# mbot_command_link.net
KiCad netlist of a schematic drawn in EasyEDA Pro
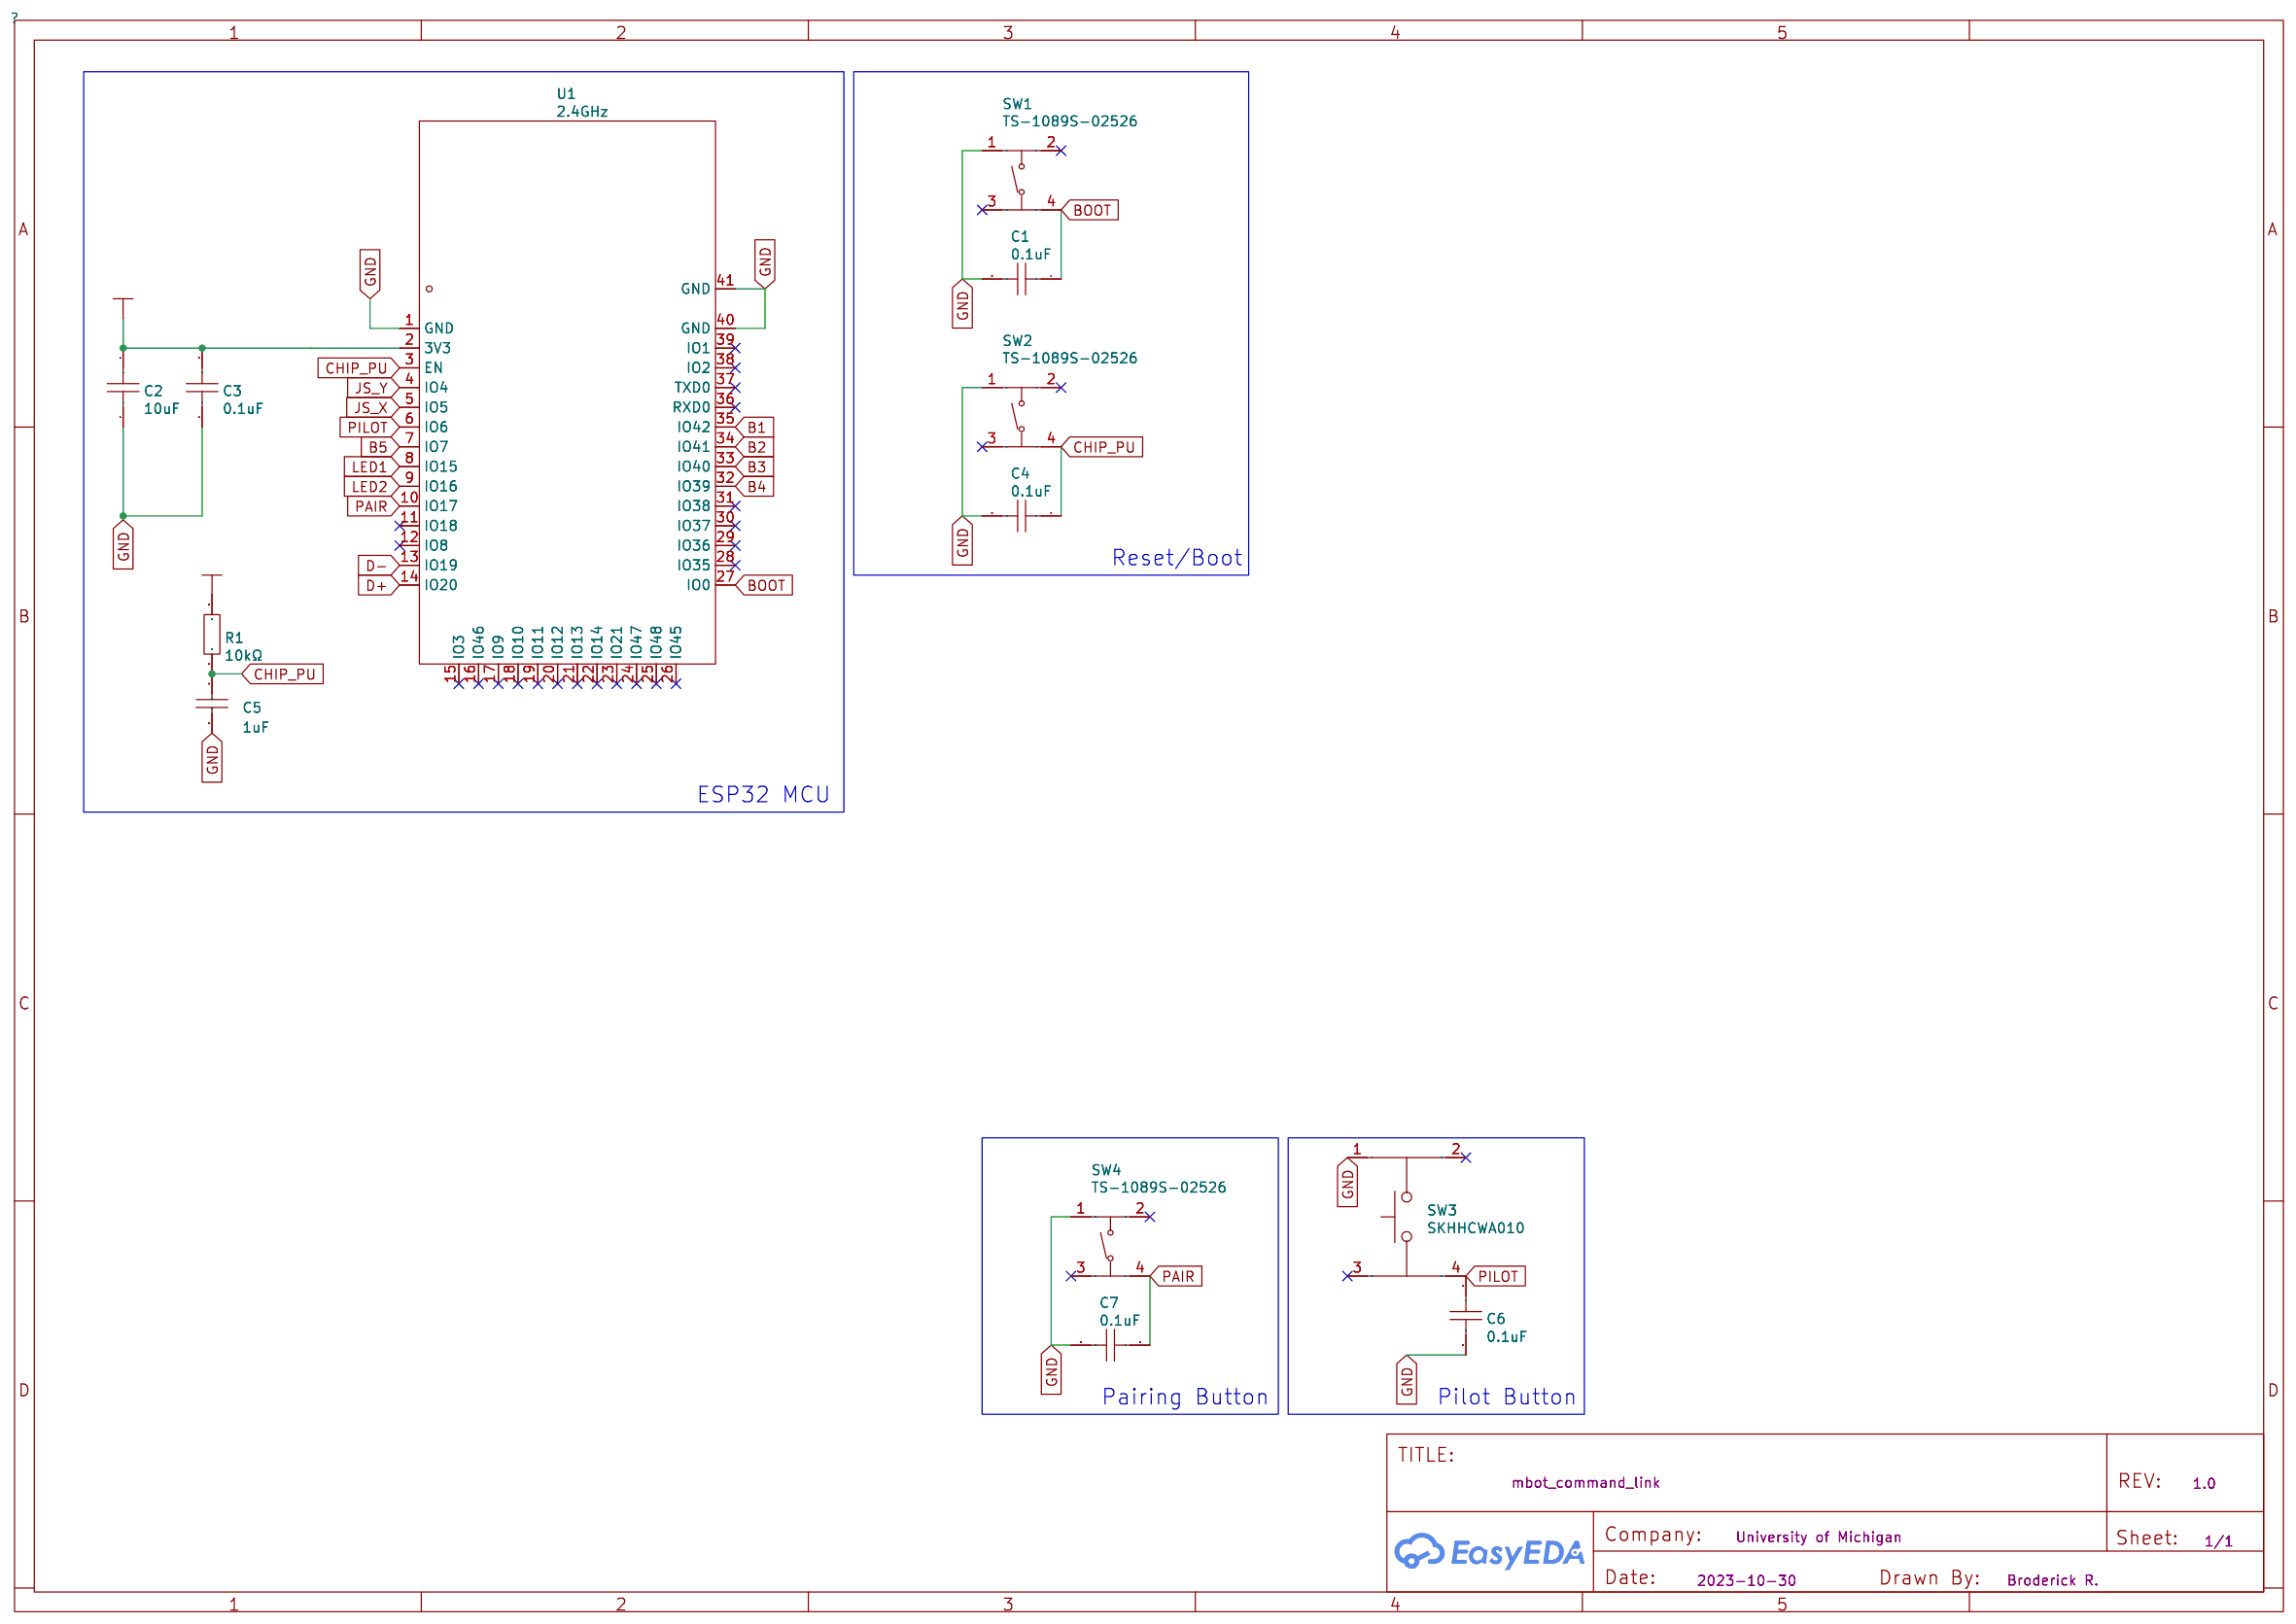
[diagram p0: MCU]
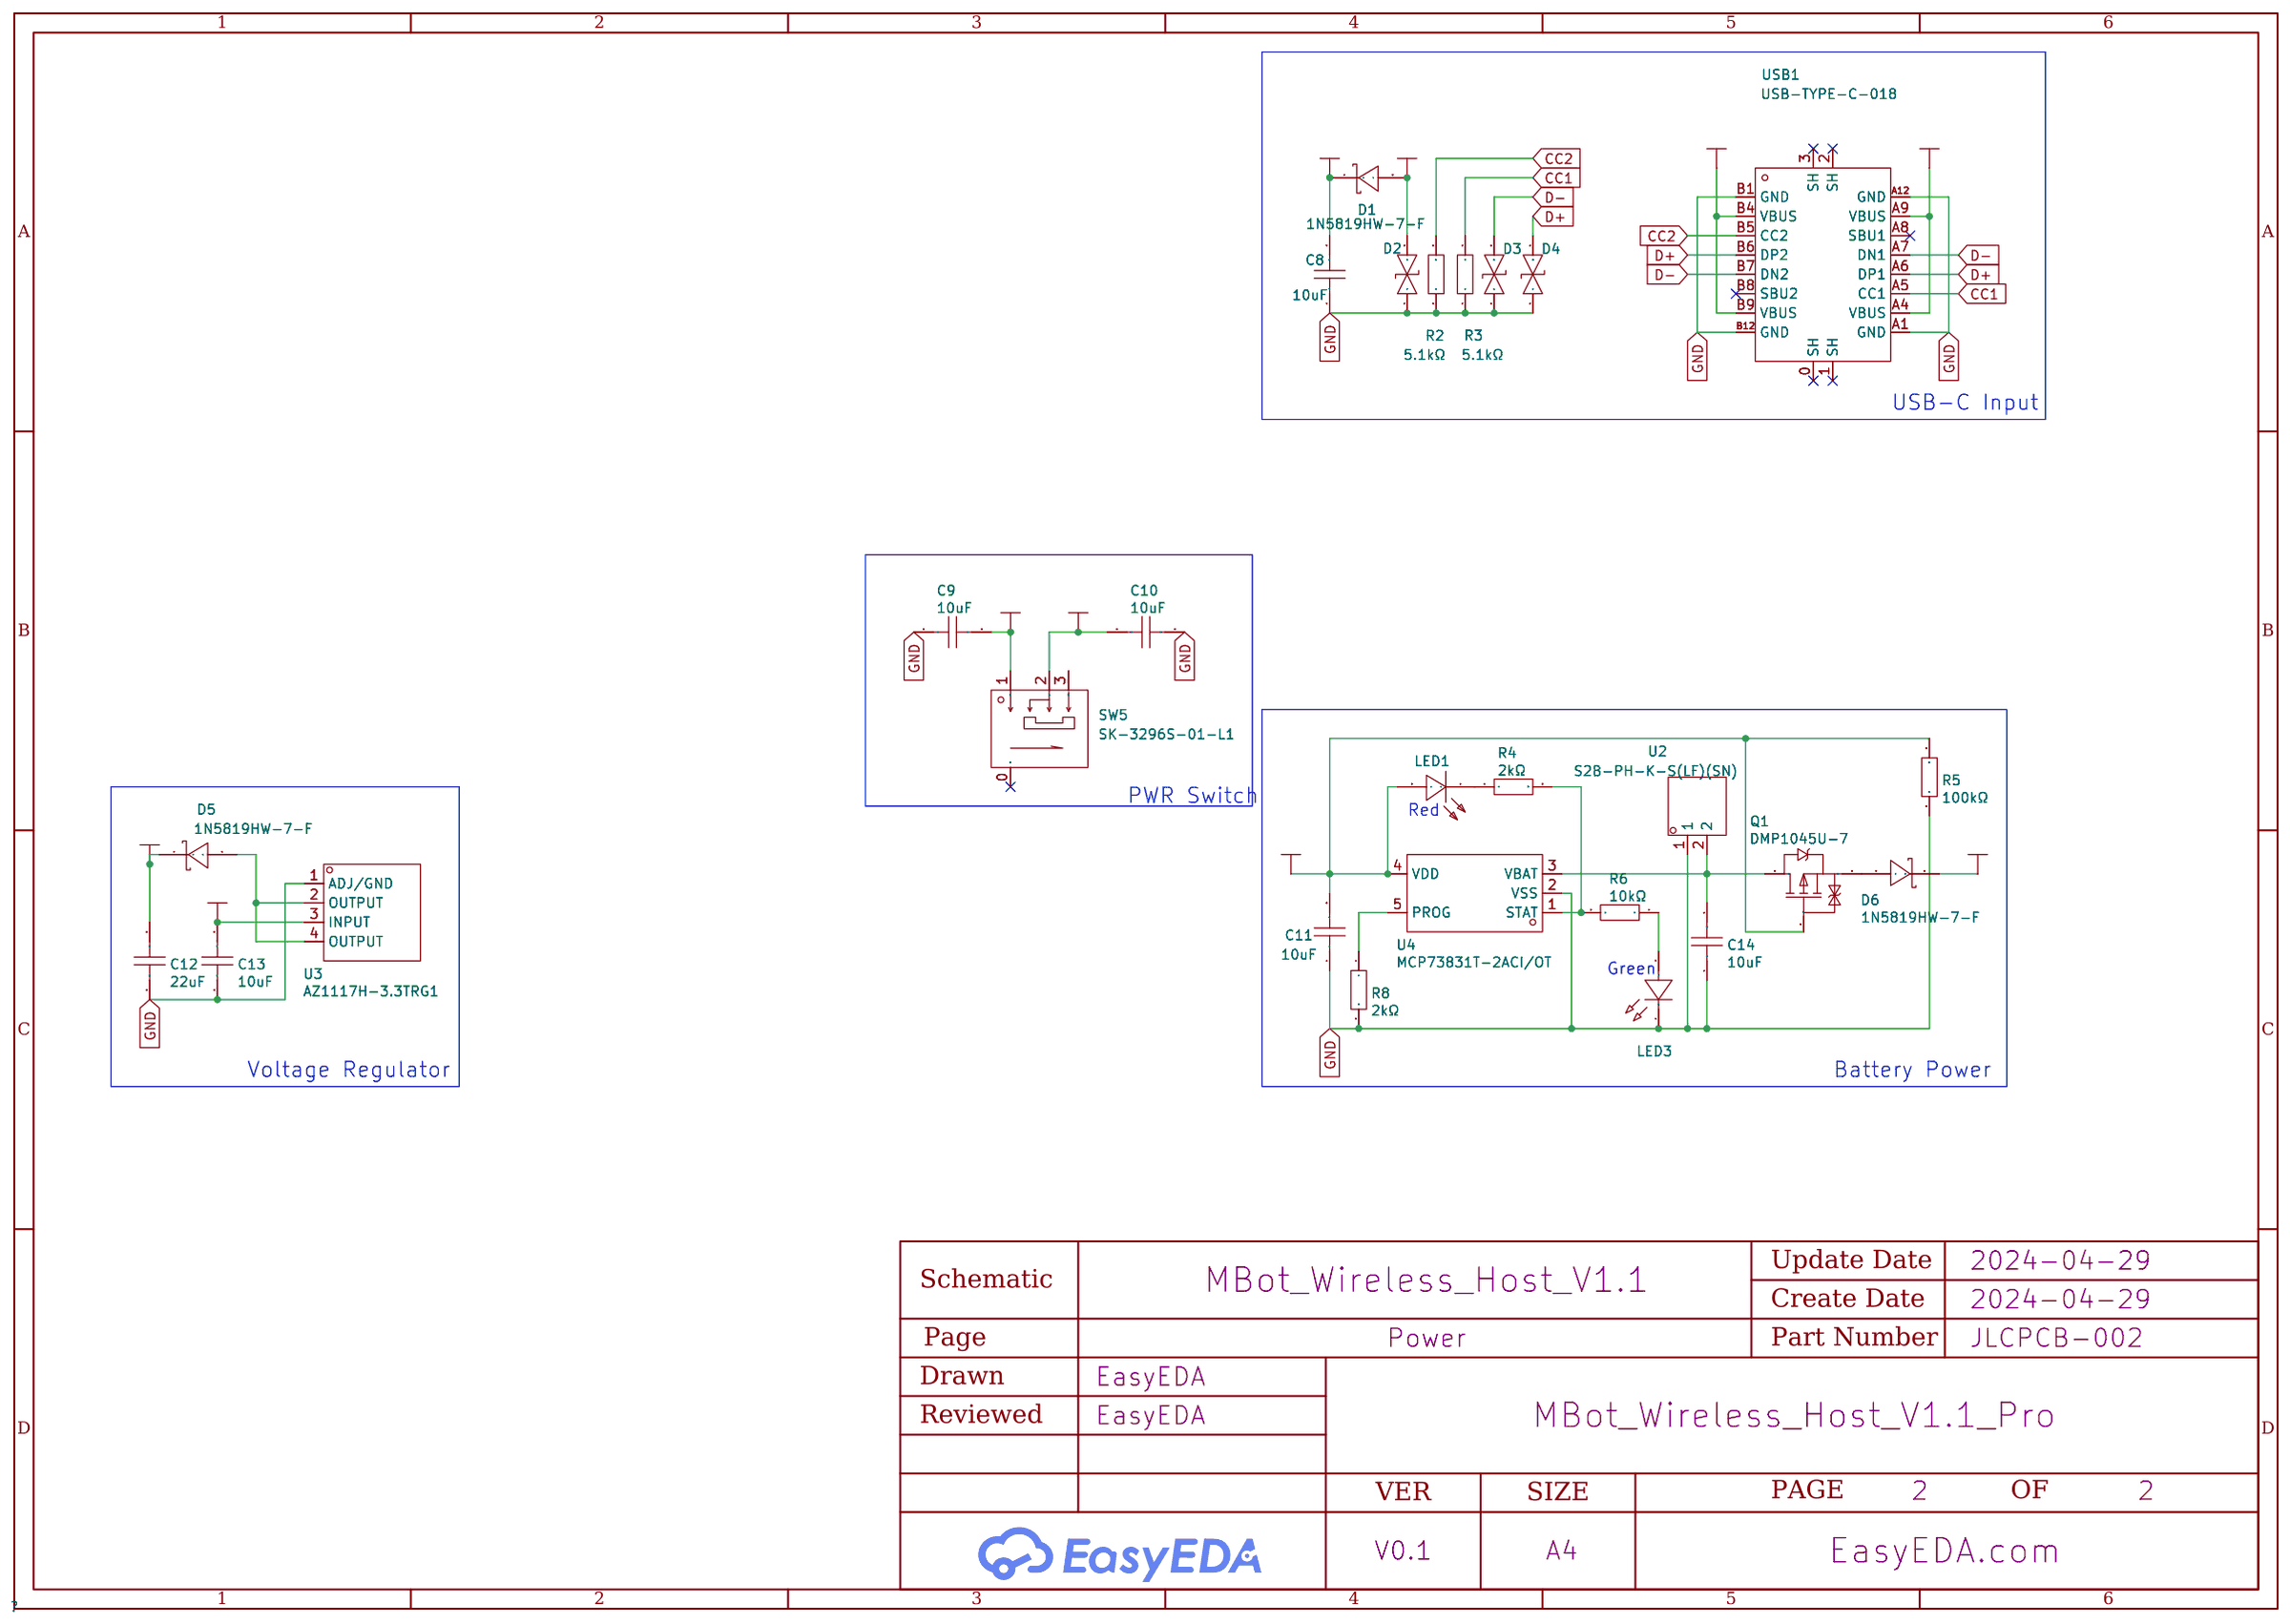
[diagram p1: Power]
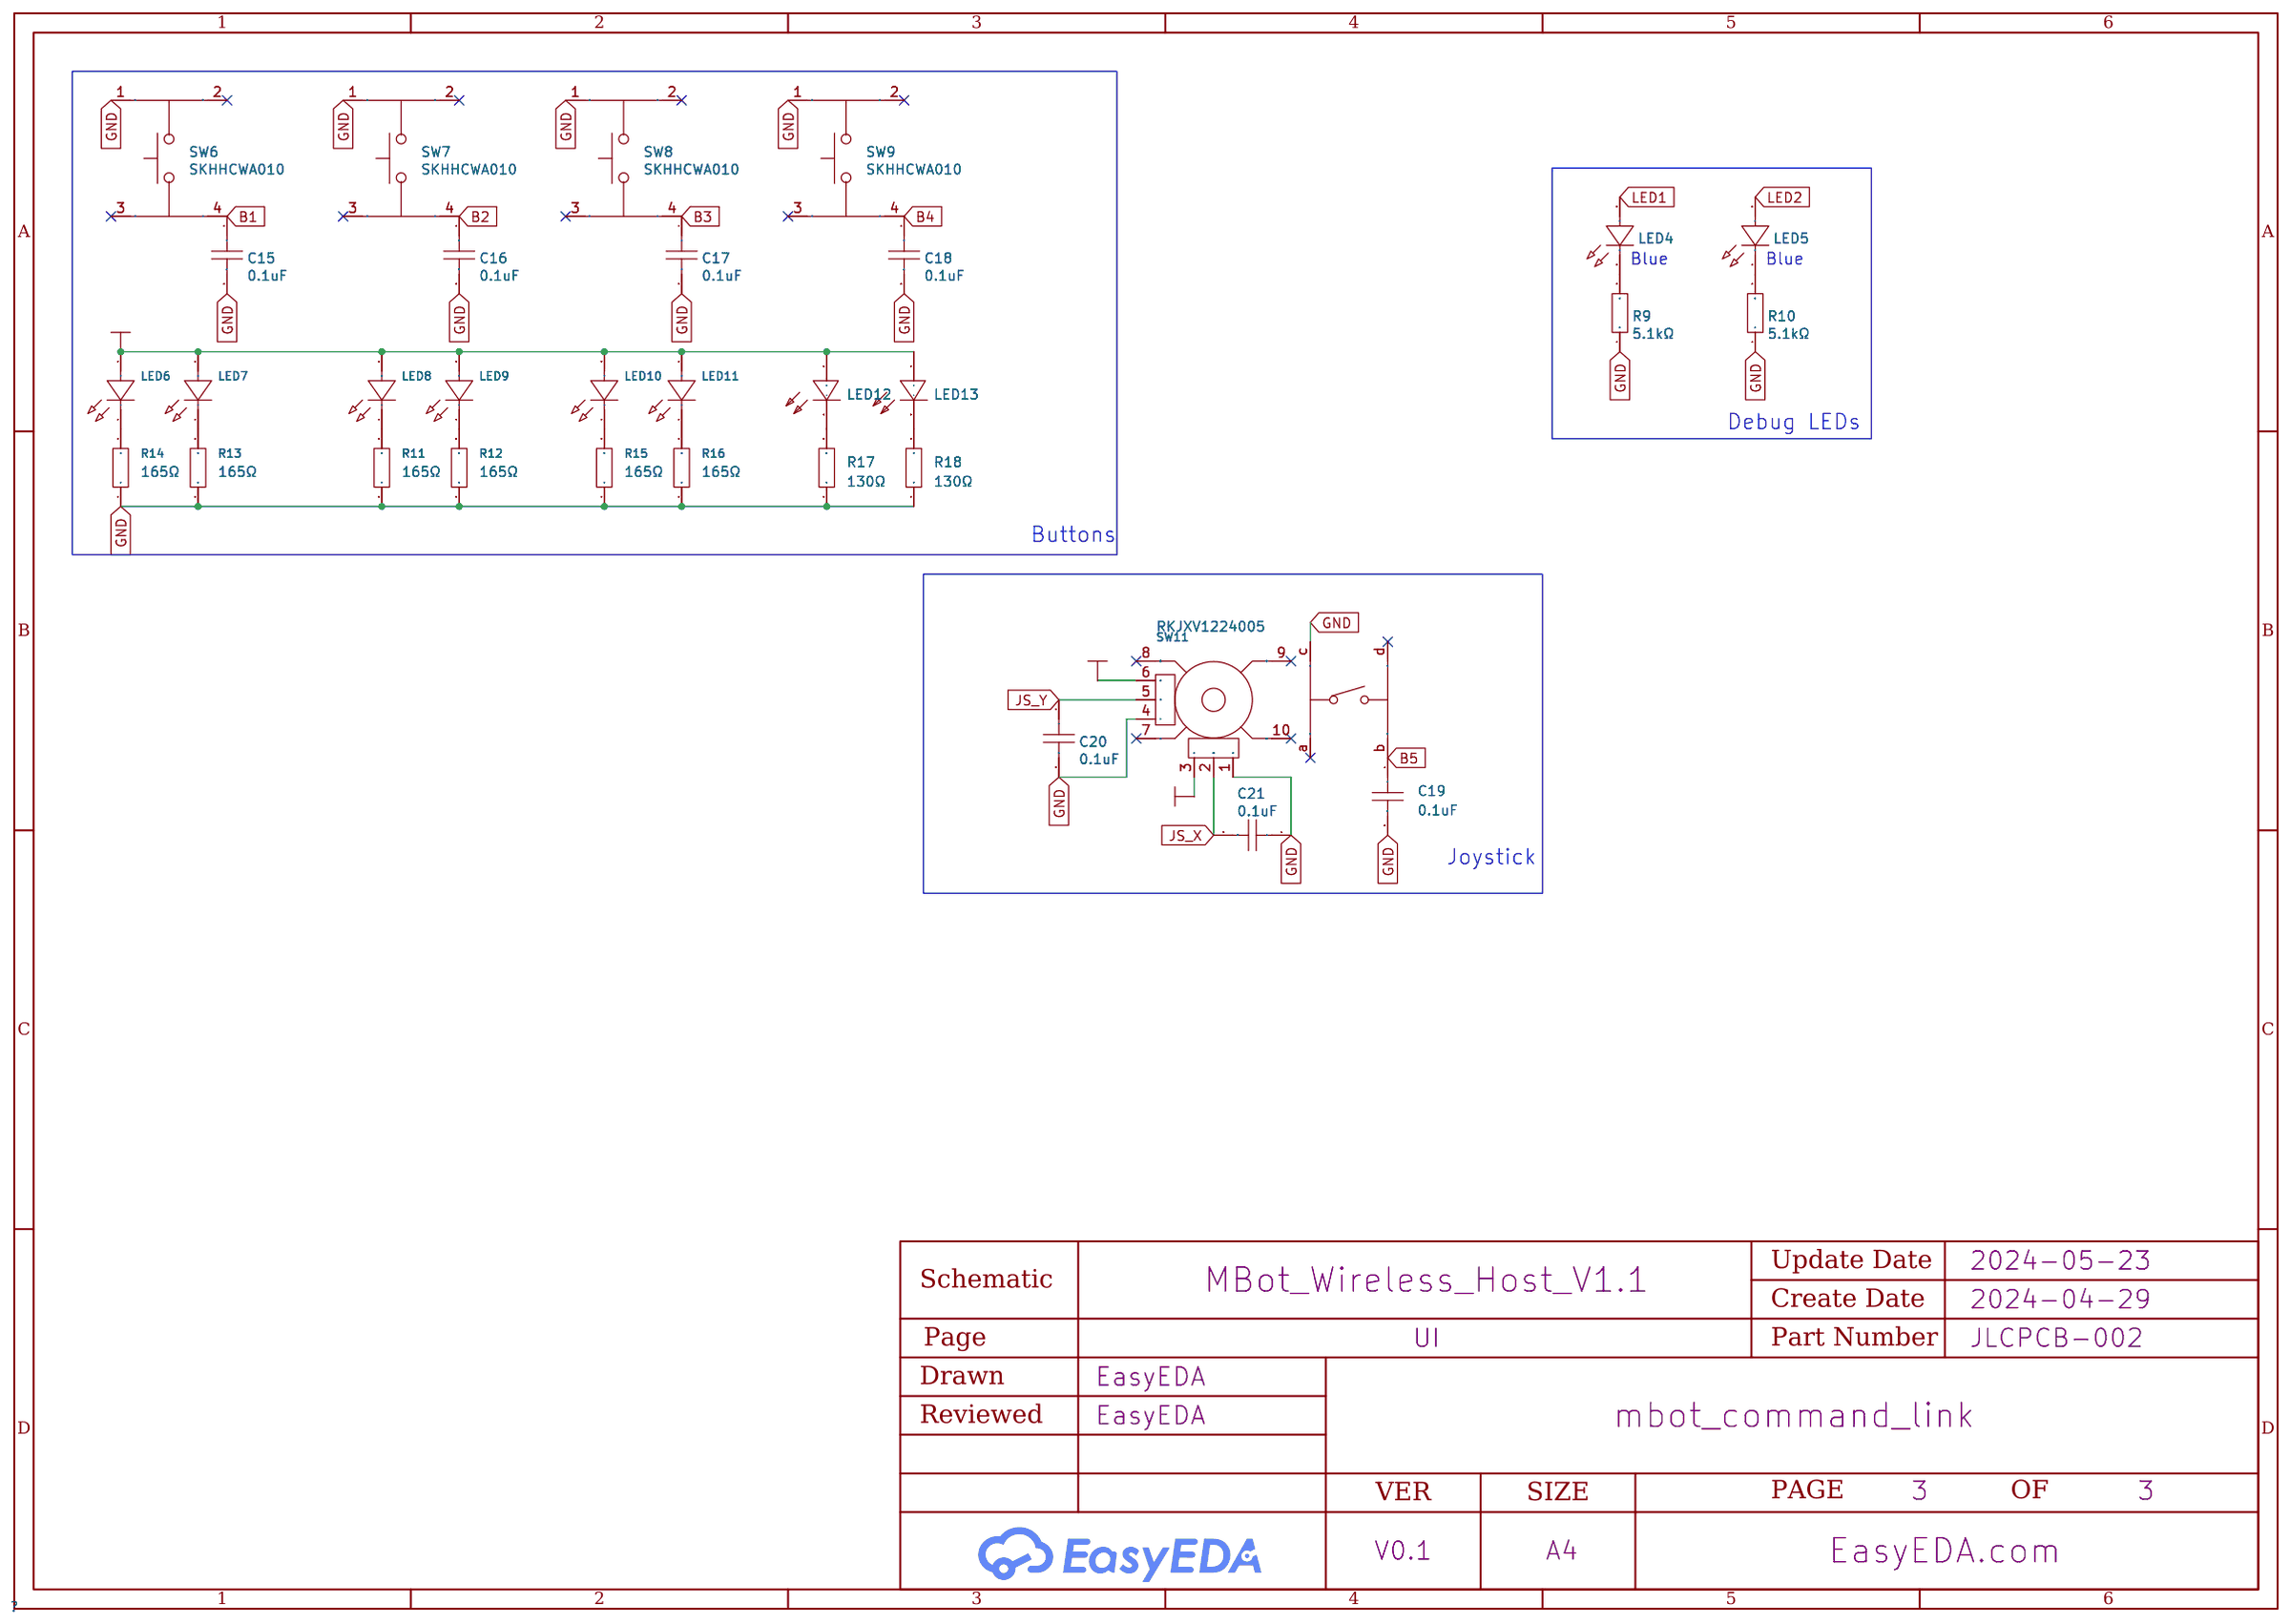
[diagram p2: UI]

(export (version "E")
  (design (tool "Eeschema 10.0.6"))
  (components
    (comp (ref "C1")
      (value "0.1uF")
      (footprint "easyedapro:footprint_52c0")
      (fields
        (field (name "Manufacturer Part") "CC0603KRX7R9BB104")
        (field (name "Manufacturer") "YAGEO(国巨)")
      )
      (libsource (lib "easyedapro") (part "0.1uF"))
    )
    (comp (ref "C2")
      (value "10uF")
      (footprint "easyedapro:footprint_52c0")
      (fields
        (field (name "Manufacturer Part") "CL10A106KP8NNNC")
        (field (name "Manufacturer") "SAMSUNG(三星)")
      )
      (libsource (lib "easyedapro") (part "10uF"))
    )
    (comp (ref "C3")
      (value "0.1uF")
      (footprint "easyedapro:footprint_52c0")
      (fields
        (field (name "Manufacturer Part") "CC0603KRX7R9BB104")
        (field (name "Manufacturer") "YAGEO(国巨)")
      )
      (libsource (lib "easyedapro") (part "0.1uF"))
    )
    (comp (ref "C4")
      (value "0.1uF")
      (footprint "easyedapro:footprint_52c0")
      (fields
        (field (name "Manufacturer Part") "CC0603KRX7R9BB104")
        (field (name "Manufacturer") "YAGEO(国巨)")
      )
      (libsource (lib "easyedapro") (part "0.1uF"))
    )
    (comp (ref "C5")
      (value "1uF")
      (footprint "easyedapro:C0603")
      (fields
        (field (name "Manufacturer Part") "CL10A105KO8NNNC")
        (field (name "Manufacturer") "SAMSUNG(三星)")
      )
      (libsource (lib "easyedapro") (part "CL10A105KO8NNNC"))
    )
    (comp (ref "C6")
      (value "0.1uF")
      (footprint "easyedapro:footprint_52c0")
      (fields
        (field (name "Manufacturer Part") "CC0603KRX7R9BB104")
        (field (name "Manufacturer") "YAGEO(国巨)")
      )
      (libsource (lib "easyedapro") (part "0.1uF"))
    )
    (comp (ref "C7")
      (value "0.1uF")
      (footprint "easyedapro:footprint_52c0")
      (fields
        (field (name "Manufacturer Part") "CC0603KRX7R9BB104")
        (field (name "Manufacturer") "YAGEO(国巨)")
      )
      (libsource (lib "easyedapro") (part "0.1uF"))
    )
    (comp (ref "R1")
      (value "10kΩ")
      (footprint "easyedapro:footprint_0432")
      (fields
        (field (name "Manufacturer Part") "0603WAF1002T5E")
        (field (name "Manufacturer") "UNI-ROYAL(厚声)")
      )
      (libsource (lib "easyedapro") (part "10kΩ"))
    )
    (comp (ref "SW1")
      (value "TS-1089S-02526")
      (footprint "easyedapro:footprint_4ab8")
      (fields (field (name "Manufacturer") "XUNPU(讯普)"))
      (libsource (lib "easyedapro") (part "TS-1089S-02526"))
    )
    (comp (ref "SW2")
      (value "TS-1089S-02526")
      (footprint "easyedapro:footprint_4ab8")
      (fields (field (name "Manufacturer") "XUNPU(讯普)"))
      (libsource (lib "easyedapro") (part "TS-1089S-02526"))
    )
    (comp (ref "SW3")
      (value "SKHHCWA010")
      (footprint "easyedapro:footprint_5a2e")
      (fields (field (name "Manufacturer") "ALPSALPINE(阿尔卑斯阿尔派)"))
      (libsource (lib "easyedapro") (part "SKHHCWA010"))
    )
    (comp (ref "SW4")
      (value "TS-1089S-02526")
      (footprint "easyedapro:footprint_4ab8")
      (fields (field (name "Manufacturer") "XUNPU(讯普)"))
      (libsource (lib "easyedapro") (part "TS-1089S-02526"))
    )
    (comp (ref "U1")
      (value "2.4GHz")
      (description "Core Processor:ESP32-S3芯片 Support Interface:I2C；GPIO；SPI；PWM；ADC；UART；USB；I2S Frequency:2.4GHz")
      (fields
        (field (name "Manufacturer Part") "ESP32-S3-WROOM-1-N8R2")
        (field (name "Manufacturer") "ESPRESSIF(乐鑫)")
      )
      (libsource (lib "easyedapro") (part "esp32-s3-wroom-1(n8r2)"))
    )
    (comp (ref "C8")
      (value "10uF")
      (footprint "easyedapro:footprint_52c0")
      (fields
        (field (name "Manufacturer Part") "CL10A106KP8NNNC")
        (field (name "Manufacturer") "SAMSUNG(三星)")
      )
      (libsource (lib "easyedapro") (part "10uF"))
    )
    (comp (ref "C9")
      (value "10uF")
      (footprint "easyedapro:footprint_52c0")
      (fields
        (field (name "Manufacturer Part") "CL10A106KP8NNNC")
        (field (name "Manufacturer") "SAMSUNG(三星)")
      )
      (libsource (lib "easyedapro") (part "10uF"))
    )
    (comp (ref "C10")
      (value "10uF")
      (footprint "easyedapro:footprint_52c0")
      (fields
        (field (name "Manufacturer Part") "CL10A106KP8NNNC")
        (field (name "Manufacturer") "SAMSUNG(三星)")
      )
      (libsource (lib "easyedapro") (part "10uF"))
    )
    (comp (ref "C11")
      (value "10uF")
      (footprint "easyedapro:footprint_52c0")
      (fields
        (field (name "Manufacturer Part") "CL10A106KP8NNNC")
        (field (name "Manufacturer") "SAMSUNG(三星)")
      )
      (libsource (lib "easyedapro") (part "10uF"))
    )
    (comp (ref "C12")
      (value "22uF")
      (footprint "easyedapro:footprint_52c0")
      (fields
        (field (name "Manufacturer Part") "CL10A226MQ8NRNC")
        (field (name "Manufacturer") "SAMSUNG(三星)")
      )
      (libsource (lib "easyedapro") (part "22uF"))
    )
    (comp (ref "C13")
      (value "10uF")
      (footprint "easyedapro:footprint_52c0")
      (fields
        (field (name "Manufacturer Part") "CL10A106KP8NNNC")
        (field (name "Manufacturer") "SAMSUNG(三星)")
      )
      (libsource (lib "easyedapro") (part "10uF"))
    )
    (comp (ref "C14")
      (value "10uF")
      (footprint "easyedapro:footprint_52c0")
      (fields
        (field (name "Manufacturer Part") "CL10A106KP8NNNC")
        (field (name "Manufacturer") "SAMSUNG(三星)")
      )
      (libsource (lib "easyedapro") (part "10uF"))
    )
    (comp (ref "D1")
      (value "1N5819HW-7-F")
      (footprint "easyedapro:footprint_34dc")
      (fields (field (name "Manufacturer") "DIODES(美台)"))
      (libsource (lib "easyedapro") (part "1N5819HW-7-F"))
    )
    (comp (ref "D2")
      (value "LESD5D5.0CT1G")
      (footprint "easyedapro:footprint_baa1")
      (fields (field (name "Manufacturer") "LRC(乐山无线电)"))
      (libsource (lib "easyedapro") (part "LESD5D5.0CT1G"))
    )
    (comp (ref "D3")
      (value "LESD5D5.0CT1G")
      (footprint "easyedapro:footprint_baa1")
      (fields (field (name "Manufacturer") "LRC(乐山无线电)"))
      (libsource (lib "easyedapro") (part "LESD5D5.0CT1G"))
    )
    (comp (ref "D4")
      (value "LESD5D5.0CT1G")
      (footprint "easyedapro:footprint_baa1")
      (fields (field (name "Manufacturer") "LRC(乐山无线电)"))
      (libsource (lib "easyedapro") (part "LESD5D5.0CT1G"))
    )
    (comp (ref "D5")
      (value "1N5819HW-7-F")
      (footprint "easyedapro:footprint_34dc")
      (fields (field (name "Manufacturer") "DIODES(美台)"))
      (libsource (lib "easyedapro") (part "1N5819HW-7-F"))
    )
    (comp (ref "D6")
      (value "1N5819HW-7-F")
      (footprint "easyedapro:footprint_34dc")
      (fields (field (name "Manufacturer") "DIODES(美台)"))
      (libsource (lib "easyedapro") (part "1N5819HW-7-F"))
    )
    (comp (ref "LED1")
      (value "KT-0603R")
      (footprint "easyedapro:footprint_1124")
      (fields (field (name "Manufacturer") "KENTO"))
      (libsource (lib "easyedapro") (part "KT-0603R"))
    )
    (comp (ref "LED3")
      (value "XL-1608UGC-04")
      (footprint "easyedapro:footprint_5fac")
      (fields (field (name "Manufacturer") "XINGLIGHT(成兴光)"))
      (libsource (lib "easyedapro") (part "XL-1608UGC-04"))
    )
    (comp (ref "Q1")
      (value "DMP1045U-7")
      (footprint "easyedapro:footprint_aab3")
      (fields (field (name "Manufacturer") "DIODES(美台)"))
      (libsource (lib "easyedapro") (part "DMP1045U-7"))
    )
    (comp (ref "R2")
      (value "5.1kΩ")
      (footprint "easyedapro:footprint_0432")
      (fields
        (field (name "Manufacturer Part") "0603WAF5101T5E")
        (field (name "Manufacturer") "UNI-ROYAL(厚声)")
      )
      (libsource (lib "easyedapro") (part "5.1kΩ"))
    )
    (comp (ref "R3")
      (value "5.1kΩ")
      (footprint "easyedapro:footprint_0432")
      (fields
        (field (name "Manufacturer Part") "0603WAF5101T5E")
        (field (name "Manufacturer") "UNI-ROYAL(厚声)")
      )
      (libsource (lib "easyedapro") (part "5.1kΩ"))
    )
    (comp (ref "R4")
      (value "2kΩ")
      (footprint "easyedapro:footprint_0432")
      (fields
        (field (name "Manufacturer Part") "0603WAF2001T5E")
        (field (name "Manufacturer") "UNI-ROYAL(厚声)")
      )
      (libsource (lib "easyedapro") (part "2kΩ"))
    )
    (comp (ref "R5")
      (value "100kΩ")
      (footprint "easyedapro:footprint_0432")
      (fields
        (field (name "Manufacturer Part") "0603WAF1003T5E")
        (field (name "Manufacturer") "UNI-ROYAL(厚声)")
      )
      (libsource (lib "easyedapro") (part "100kΩ"))
    )
    (comp (ref "R6")
      (value "10kΩ")
      (footprint "easyedapro:footprint_0432")
      (fields
        (field (name "Manufacturer Part") "0603WAF1002T5E")
        (field (name "Manufacturer") "UNI-ROYAL(厚声)")
      )
      (libsource (lib "easyedapro") (part "10kΩ"))
    )
    (comp (ref "R8")
      (value "2kΩ")
      (footprint "easyedapro:footprint_0432")
      (fields
        (field (name "Manufacturer Part") "0603WAF2001T5E")
        (field (name "Manufacturer") "UNI-ROYAL(厚声)")
      )
      (libsource (lib "easyedapro") (part "2kΩ"))
    )
    (comp (ref "SW5")
      (value "SK-3296S-01-L1")
      (footprint "easyedapro:SW-SMD_3P-P1.50_L2.7-W6.6")
      (fields (field (name "Manufacturer") "XKB Connectivity(中国星坤)"))
      (libsource (lib "easyedapro") (part "SK-3296S-01-L1"))
    )
    (comp (ref "U2")
      (value "S2B-PH-K-S(LF)(SN)")
      (footprint "easyedapro:footprint_2180")
      (fields (field (name "Manufacturer") "JST"))
      (libsource (lib "easyedapro") (part "S2B-PH-K-S(LF)(SN)"))
    )
    (comp (ref "U3")
      (value "AZ1117H-3.3TRG1")
      (footprint "easyedapro:footprint_7102")
      (fields (field (name "Manufacturer") "DIODES(美台)"))
      (libsource (lib "easyedapro") (part "AZ1117H-3.3TRG1"))
    )
    (comp (ref "U4")
      (value "MCP73831T-2ACI/OT")
      (footprint "easyedapro:footprint_d70e")
      (fields (field (name "Manufacturer") "MICROCHIP(美国微芯)"))
      (libsource (lib "easyedapro") (part "MCP73831T-2ACI/OT"))
    )
    (comp (ref "USB1")
      (value "USB-TYPE-C-018")
      (footprint "easyedapro:footprint_530a")
      (fields (field (name "Manufacturer") "DEALON(德艺隆)"))
      (libsource (lib "easyedapro") (part "USB-TYPE-C-018"))
    )
    (comp (ref "C15")
      (value "0.1uF")
      (footprint "easyedapro:footprint_52c0")
      (fields
        (field (name "Manufacturer Part") "CC0603KRX7R9BB104")
        (field (name "Manufacturer") "YAGEO(国巨)")
      )
      (libsource (lib "easyedapro") (part "0.1uF"))
    )
    (comp (ref "C16")
      (value "0.1uF")
      (footprint "easyedapro:footprint_52c0")
      (fields
        (field (name "Manufacturer Part") "CC0603KRX7R9BB104")
        (field (name "Manufacturer") "YAGEO(国巨)")
      )
      (libsource (lib "easyedapro") (part "0.1uF"))
    )
    (comp (ref "C17")
      (value "0.1uF")
      (footprint "easyedapro:footprint_52c0")
      (fields
        (field (name "Manufacturer Part") "CC0603KRX7R9BB104")
        (field (name "Manufacturer") "YAGEO(国巨)")
      )
      (libsource (lib "easyedapro") (part "0.1uF"))
    )
    (comp (ref "C18")
      (value "0.1uF")
      (footprint "easyedapro:footprint_52c0")
      (fields
        (field (name "Manufacturer Part") "CC0603KRX7R9BB104")
        (field (name "Manufacturer") "YAGEO(国巨)")
      )
      (libsource (lib "easyedapro") (part "0.1uF"))
    )
    (comp (ref "C19")
      (value "0.1uF")
      (footprint "easyedapro:footprint_52c0")
      (fields
        (field (name "Manufacturer Part") "CC0603KRX7R9BB104")
        (field (name "Manufacturer") "YAGEO(国巨)")
      )
      (libsource (lib "easyedapro") (part "0.1uF"))
    )
    (comp (ref "C20")
      (value "0.1uF")
      (footprint "easyedapro:footprint_52c0")
      (fields
        (field (name "Manufacturer Part") "CC0603KRX7R9BB104")
        (field (name "Manufacturer") "YAGEO(国巨)")
      )
      (libsource (lib "easyedapro") (part "0.1uF"))
    )
    (comp (ref "C21")
      (value "0.1uF")
      (footprint "easyedapro:footprint_52c0")
      (fields
        (field (name "Manufacturer Part") "CC0603KRX7R9BB104")
        (field (name "Manufacturer") "YAGEO(国巨)")
      )
      (libsource (lib "easyedapro") (part "0.1uF"))
    )
    (comp (ref "LED4")
      (value "XL-1608UBC-04")
      (fields (field (name "Manufacturer") "XINGLIGHT(成兴光)"))
      (libsource (lib "easyedapro") (part "xl-1608ubc-04"))
    )
    (comp (ref "LED5")
      (value "XL-1608UBC-04")
      (fields (field (name "Manufacturer") "XINGLIGHT(成兴光)"))
      (libsource (lib "easyedapro") (part "xl-1608ubc-04"))
    )
    (comp (ref "LED6")
      (value "XL-1608UYC-06")
      (footprint "easyedapro:LED0603-RD-YELLOW")
      (fields (field (name "Manufacturer") "XINGLIGHT(成兴光)"))
      (libsource (lib "easyedapro") (part "XL-1608UYC-06"))
    )
    (comp (ref "LED7")
      (value "XL-1608UYC-06")
      (footprint "easyedapro:LED0603-RD-YELLOW")
      (fields (field (name "Manufacturer") "XINGLIGHT(成兴光)"))
      (libsource (lib "easyedapro") (part "XL-1608UYC-06"))
    )
    (comp (ref "LED8")
      (value "XL-1608SURC-06")
      (footprint "easyedapro:LED0603-RD_RED")
      (fields (field (name "Manufacturer") "XINGLIGHT(成兴光)"))
      (libsource (lib "easyedapro") (part "XL-1608SURC-06"))
    )
    (comp (ref "LED9")
      (value "XL-1608SURC-06")
      (footprint "easyedapro:LED0603-RD_RED")
      (fields (field (name "Manufacturer") "XINGLIGHT(成兴光)"))
      (libsource (lib "easyedapro") (part "XL-1608SURC-06"))
    )
    (comp (ref "LED10")
      (value "XL-1608UGC-04")
      (footprint "easyedapro:LED0603-RD_GREEN")
      (fields (field (name "Manufacturer") "XINGLIGHT(成兴光)"))
      (libsource (lib "easyedapro") (part "XL-1608UGC-04"))
    )
    (comp (ref "LED11")
      (value "XL-1608UGC-04")
      (footprint "easyedapro:LED0603-RD_GREEN")
      (fields (field (name "Manufacturer") "XINGLIGHT(成兴光)"))
      (libsource (lib "easyedapro") (part "XL-1608UGC-04"))
    )
    (comp (ref "LED12")
      (value "19-218/BHC-ZL1M2QY/3T")
      (footprint "easyedapro:footprint_f0ed")
      (fields (field (name "Manufacturer") "EVERLIGHT(亿光)"))
      (libsource (lib "easyedapro") (part "19-218/BHC-ZL1M2QY/3T"))
    )
    (comp (ref "LED13")
      (value "19-218/BHC-ZL1M2QY/3T")
      (footprint "easyedapro:footprint_f0ed")
      (fields (field (name "Manufacturer") "EVERLIGHT(亿光)"))
      (libsource (lib "easyedapro") (part "19-218/BHC-ZL1M2QY/3T"))
    )
    (comp (ref "R9")
      (value "5.1kΩ")
      (footprint "easyedapro:footprint_0432")
      (fields
        (field (name "Manufacturer Part") "0603WAF5101T5E")
        (field (name "Manufacturer") "UNI-ROYAL(厚声)")
      )
      (libsource (lib "easyedapro") (part "5.1kΩ"))
    )
    (comp (ref "R10")
      (value "5.1kΩ")
      (footprint "easyedapro:footprint_0432")
      (fields
        (field (name "Manufacturer Part") "0603WAF5101T5E")
        (field (name "Manufacturer") "UNI-ROYAL(厚声)")
      )
      (libsource (lib "easyedapro") (part "5.1kΩ"))
    )
    (comp (ref "R11")
      (value "165Ω")
      (footprint "easyedapro:R0603")
      (fields
        (field (name "Manufacturer Part") "0603WAF1650T5E")
        (field (name "Manufacturer") "UNI-ROYAL(厚声)")
      )
      (libsource (lib "easyedapro") (part "0603WAF1650T5E"))
    )
    (comp (ref "R12")
      (value "165Ω")
      (footprint "easyedapro:R0603")
      (fields
        (field (name "Manufacturer Part") "0603WAF1650T5E")
        (field (name "Manufacturer") "UNI-ROYAL(厚声)")
      )
      (libsource (lib "easyedapro") (part "0603WAF1650T5E"))
    )
    (comp (ref "R13")
      (value "165Ω")
      (footprint "easyedapro:R0603")
      (fields
        (field (name "Manufacturer Part") "0603WAF1650T5E")
        (field (name "Manufacturer") "UNI-ROYAL(厚声)")
      )
      (libsource (lib "easyedapro") (part "0603WAF1650T5E"))
    )
    (comp (ref "R14")
      (value "165Ω")
      (footprint "easyedapro:R0603")
      (fields
        (field (name "Manufacturer Part") "0603WAF1650T5E")
        (field (name "Manufacturer") "UNI-ROYAL(厚声)")
      )
      (libsource (lib "easyedapro") (part "0603WAF1650T5E"))
    )
    (comp (ref "R15")
      (value "165Ω")
      (footprint "easyedapro:R0603")
      (fields
        (field (name "Manufacturer Part") "0603WAF1650T5E")
        (field (name "Manufacturer") "UNI-ROYAL(厚声)")
      )
      (libsource (lib "easyedapro") (part "0603WAF1650T5E"))
    )
    (comp (ref "R16")
      (value "165Ω")
      (footprint "easyedapro:R0603")
      (fields
        (field (name "Manufacturer Part") "0603WAF1650T5E")
        (field (name "Manufacturer") "UNI-ROYAL(厚声)")
      )
      (libsource (lib "easyedapro") (part "0603WAF1650T5E"))
    )
    (comp (ref "R17")
      (value "130Ω")
      (footprint "easyedapro:R0603")
      (fields
        (field (name "Manufacturer Part") "0603WAF1300T5E")
        (field (name "Manufacturer") "UNI-ROYAL(厚声)")
      )
      (libsource (lib "easyedapro") (part "0603WAF1300T5E"))
    )
    (comp (ref "R18")
      (value "130Ω")
      (footprint "easyedapro:R0603")
      (fields
        (field (name "Manufacturer Part") "0603WAF1300T5E")
        (field (name "Manufacturer") "UNI-ROYAL(厚声)")
      )
      (libsource (lib "easyedapro") (part "0603WAF1300T5E"))
    )
    (comp (ref "SW6")
      (value "SKHHCWA010")
      (footprint "easyedapro:footprint_5a2e")
      (fields (field (name "Manufacturer") "ALPSALPINE(阿尔卑斯阿尔派)"))
      (libsource (lib "easyedapro") (part "SKHHCWA010"))
    )
    (comp (ref "SW7")
      (value "SKHHCWA010")
      (footprint "easyedapro:footprint_5a2e")
      (fields (field (name "Manufacturer") "ALPSALPINE(阿尔卑斯阿尔派)"))
      (libsource (lib "easyedapro") (part "SKHHCWA010"))
    )
    (comp (ref "SW8")
      (value "SKHHCWA010")
      (footprint "easyedapro:footprint_5a2e")
      (fields (field (name "Manufacturer") "ALPSALPINE(阿尔卑斯阿尔派)"))
      (libsource (lib "easyedapro") (part "SKHHCWA010"))
    )
    (comp (ref "SW9")
      (value "SKHHCWA010")
      (footprint "easyedapro:footprint_5a2e")
      (fields (field (name "Manufacturer") "ALPSALPINE(阿尔卑斯阿尔派)"))
      (libsource (lib "easyedapro") (part "SKHHCWA010"))
    )
    (comp (ref "SW11")
      (value "RKJXV1224005")
      (footprint "easyedapro:SW-TH_RKJXV1224005")
      (fields (field (name "Manufacturer") "ALPSALPINE(阿尔卑斯阿尔派)"))
      (libsource (lib "easyedapro") (part "RKJXV1224005"))
    )
  )
  (nets
    (net (code "1") (name "3V3") (class "Default")
      (node (ref "C12") (pin "2") (pinfunction "2_2") (pintype "unspecified"))
      (node (ref "C2") (pin "2") (pinfunction "2_2") (pintype "unspecified"))
      (node (ref "C3") (pin "2") (pinfunction "2_2") (pintype "unspecified"))
      (node (ref "D5") (pin "1") (pinfunction "K_1") (pintype "unspecified"))
      (node (ref "LED10") (pin "2") (pinfunction "A_2") (pintype "input"))
      (node (ref "LED11") (pin "2") (pinfunction "A_2") (pintype "input"))
      (node (ref "LED12") (pin "1") (pinfunction "+_1") (pintype "unspecified"))
      (node (ref "LED13") (pin "1") (pinfunction "+_1") (pintype "unspecified"))
      (node (ref "LED6") (pin "2") (pinfunction "A_2") (pintype "input"))
      (node (ref "LED7") (pin "2") (pinfunction "A_2") (pintype "input"))
      (node (ref "LED8") (pin "2") (pinfunction "A_2") (pintype "input"))
      (node (ref "LED9") (pin "2") (pinfunction "A_2") (pintype "input"))
      (node (ref "R1") (pin "2") (pinfunction "2_2") (pintype "input"))
      (node (ref "SW11") (pin "3") (pinfunction "A_3") (pintype "input"))
      (node (ref "SW11") (pin "6") (pinfunction "B_6") (pintype "input"))
      (node (ref "U1") (pin "2") (pinfunction "3V3_2") (pintype "unspecified"))
    )
    (net (code "2") (name "B1") (class "Default")
      (node (ref "C15") (pin "1") (pinfunction "1_1") (pintype "unspecified"))
      (node (ref "SW6") (pin "4") (pinfunction "4_4") (pintype "unspecified"))
      (node (ref "U1") (pin "35") (pinfunction "IO42_35") (pintype "unspecified"))
    )
    (net (code "3") (name "B2") (class "Default")
      (node (ref "C16") (pin "1") (pinfunction "1_1") (pintype "unspecified"))
      (node (ref "SW7") (pin "4") (pinfunction "4_4") (pintype "unspecified"))
      (node (ref "U1") (pin "34") (pinfunction "IO41_34") (pintype "unspecified"))
    )
    (net (code "4") (name "B3") (class "Default")
      (node (ref "C17") (pin "1") (pinfunction "1_1") (pintype "unspecified"))
      (node (ref "SW8") (pin "4") (pinfunction "4_4") (pintype "unspecified"))
      (node (ref "U1") (pin "33") (pinfunction "IO40_33") (pintype "unspecified"))
    )
    (net (code "5") (name "B4") (class "Default")
      (node (ref "C18") (pin "1") (pinfunction "1_1") (pintype "unspecified"))
      (node (ref "SW9") (pin "4") (pinfunction "4_4") (pintype "unspecified"))
      (node (ref "U1") (pin "32") (pinfunction "IO39_32") (pintype "unspecified"))
    )
    (net (code "6") (name "B5") (class "Default")
      (node (ref "C19") (pin "1") (pinfunction "1_1") (pintype "unspecified"))
      (node (ref "SW11") (pin "b") (pinfunction "b_b") (pintype "input"))
      (node (ref "U1") (pin "7") (pinfunction "IO7_7") (pintype "unspecified"))
    )
    (net (code "7") (name "BOOT") (class "Default")
      (node (ref "C1") (pin "1") (pinfunction "1_1") (pintype "unspecified"))
      (node (ref "SW1") (pin "4") (pinfunction "4_4") (pintype "unspecified"))
      (node (ref "U1") (pin "27") (pinfunction "IO0_27") (pintype "unspecified"))
    )
    (net (code "8") (name "CC1") (class "Default")
      (node (ref "R3") (pin "2") (pinfunction "2_2") (pintype "input"))
      (node (ref "USB1") (pin "A5") (pinfunction "CC1_A5") (pintype "unspecified"))
    )
    (net (code "9") (name "CC2") (class "Default")
      (node (ref "R2") (pin "2") (pinfunction "2_2") (pintype "input"))
      (node (ref "USB1") (pin "B5") (pinfunction "CC2_B5") (pintype "unspecified"))
    )
    (net (code "10") (name "CHIP_PU") (class "Default")
      (node (ref "C4") (pin "1") (pinfunction "1_1") (pintype "unspecified"))
      (node (ref "C5") (pin "2") (pinfunction "2_2") (pintype "input"))
      (node (ref "R1") (pin "1") (pinfunction "1_1") (pintype "input"))
      (node (ref "SW2") (pin "4") (pinfunction "4_4") (pintype "unspecified"))
      (node (ref "U1") (pin "3") (pinfunction "EN_3") (pintype "unspecified"))
    )
    (net (code "11") (name "D+") (class "Default")
      (node (ref "D4") (pin "2") (pinfunction "2_2") (pintype "unspecified"))
      (node (ref "U1") (pin "14") (pinfunction "IO20_14") (pintype "unspecified"))
      (node (ref "USB1") (pin "A6") (pinfunction "DP1_A6") (pintype "unspecified"))
      (node (ref "USB1") (pin "B6") (pinfunction "DP2_B6") (pintype "unspecified"))
    )
    (net (code "12") (name "D-") (class "Default")
      (node (ref "D3") (pin "2") (pinfunction "2_2") (pintype "unspecified"))
      (node (ref "U1") (pin "13") (pinfunction "IO19_13") (pintype "unspecified"))
      (node (ref "USB1") (pin "A7") (pinfunction "DN1_A7") (pintype "unspecified"))
      (node (ref "USB1") (pin "B7") (pinfunction "DN2_B7") (pintype "unspecified"))
    )
    (net (code "13") (name "GND") (class "Default")
      (node (ref "C1") (pin "2") (pinfunction "2_2") (pintype "unspecified"))
      (node (ref "C10") (pin "1") (pinfunction "1_1") (pintype "unspecified"))
      (node (ref "C11") (pin "1") (pinfunction "1_1") (pintype "unspecified"))
      (node (ref "C12") (pin "1") (pinfunction "1_1") (pintype "unspecified"))
      (node (ref "C13") (pin "1") (pinfunction "1_1") (pintype "unspecified"))
      (node (ref "C14") (pin "1") (pinfunction "1_1") (pintype "unspecified"))
      (node (ref "C15") (pin "2") (pinfunction "2_2") (pintype "unspecified"))
      (node (ref "C16") (pin "2") (pinfunction "2_2") (pintype "unspecified"))
      (node (ref "C17") (pin "2") (pinfunction "2_2") (pintype "unspecified"))
      (node (ref "C18") (pin "2") (pinfunction "2_2") (pintype "unspecified"))
      (node (ref "C19") (pin "2") (pinfunction "2_2") (pintype "unspecified"))
      (node (ref "C2") (pin "1") (pinfunction "1_1") (pintype "unspecified"))
      (node (ref "C20") (pin "2") (pinfunction "2_2") (pintype "unspecified"))
      (node (ref "C21") (pin "1") (pinfunction "1_1") (pintype "unspecified"))
      (node (ref "C3") (pin "1") (pinfunction "1_1") (pintype "unspecified"))
      (node (ref "C4") (pin "2") (pinfunction "2_2") (pintype "unspecified"))
      (node (ref "C5") (pin "1") (pinfunction "1_1") (pintype "input"))
      (node (ref "C6") (pin "2") (pinfunction "2_2") (pintype "unspecified"))
      (node (ref "C7") (pin "2") (pinfunction "2_2") (pintype "unspecified"))
      (node (ref "C8") (pin "1") (pinfunction "1_1") (pintype "unspecified"))
      (node (ref "C9") (pin "1") (pinfunction "1_1") (pintype "unspecified"))
      (node (ref "D2") (pin "1") (pinfunction "1_1") (pintype "unspecified"))
      (node (ref "D3") (pin "1") (pinfunction "1_1") (pintype "unspecified"))
      (node (ref "D4") (pin "1") (pinfunction "1_1") (pintype "unspecified"))
      (node (ref "LED3") (pin "1") (pinfunction "K_1") (pintype "unspecified"))
      (node (ref "R10") (pin "1") (pinfunction "1_1") (pintype "input"))
      (node (ref "R11") (pin "1") (pinfunction "1_1") (pintype "input"))
      (node (ref "R12") (pin "1") (pinfunction "1_1") (pintype "input"))
      (node (ref "R13") (pin "1") (pinfunction "1_1") (pintype "input"))
      (node (ref "R14") (pin "1") (pinfunction "1_1") (pintype "input"))
      (node (ref "R15") (pin "1") (pinfunction "1_1") (pintype "input"))
      (node (ref "R16") (pin "1") (pinfunction "1_1") (pintype "input"))
      (node (ref "R17") (pin "1") (pinfunction "1_1") (pintype "input"))
      (node (ref "R18") (pin "1") (pinfunction "1_1") (pintype "input"))
      (node (ref "R2") (pin "1") (pinfunction "1_1") (pintype "input"))
      (node (ref "R3") (pin "1") (pinfunction "1_1") (pintype "input"))
      (node (ref "R5") (pin "1") (pinfunction "1_1") (pintype "input"))
      (node (ref "R8") (pin "2") (pinfunction "2_2") (pintype "input"))
      (node (ref "R9") (pin "1") (pinfunction "1_1") (pintype "input"))
      (node (ref "SW1") (pin "1") (pinfunction "1_1") (pintype "unspecified"))
      (node (ref "SW11") (pin "1") (pinfunction "B_1") (pintype "input"))
      (node (ref "SW11") (pin "4") (pinfunction "A_4") (pintype "input"))
      (node (ref "SW11") (pin "c") (pinfunction "c_c") (pintype "input"))
      (node (ref "SW2") (pin "1") (pinfunction "1_1") (pintype "unspecified"))
      (node (ref "SW3") (pin "1") (pinfunction "1_1") (pintype "unspecified"))
      (node (ref "SW4") (pin "1") (pinfunction "1_1") (pintype "unspecified"))
      (node (ref "SW6") (pin "1") (pinfunction "1_1") (pintype "unspecified"))
      (node (ref "SW7") (pin "1") (pinfunction "1_1") (pintype "unspecified"))
      (node (ref "SW8") (pin "1") (pinfunction "1_1") (pintype "unspecified"))
      (node (ref "SW9") (pin "1") (pinfunction "1_1") (pintype "unspecified"))
      (node (ref "U1") (pin "1") (pinfunction "GND_1") (pintype "unspecified"))
      (node (ref "U1") (pin "40") (pinfunction "GND_40") (pintype "unspecified"))
      (node (ref "U1") (pin "41") (pinfunction "GND_41") (pintype "unspecified"))
      (node (ref "U2") (pin "1") (pinfunction "1_1") (pintype "unspecified"))
      (node (ref "U3") (pin "1") (pinfunction "ADJ/GND_1") (pintype "unspecified"))
      (node (ref "U4") (pin "2") (pinfunction "VSS_2") (pintype "unspecified"))
      (node (ref "USB1") (pin "A1") (pinfunction "GND_A1") (pintype "unspecified"))
      (node (ref "USB1") (pin "A12") (pinfunction "GND_A12") (pintype "unspecified"))
      (node (ref "USB1") (pin "B1") (pinfunction "GND_B1") (pintype "unspecified"))
      (node (ref "USB1") (pin "B12") (pinfunction "GND_B12") (pintype "unspecified"))
    )
    (net (code "14") (name "JS_X") (class "Default")
      (node (ref "C21") (pin "2") (pinfunction "2_2") (pintype "unspecified"))
      (node (ref "SW11") (pin "2") (pinfunction "DTA_2") (pintype "input"))
      (node (ref "U1") (pin "5") (pinfunction "IO5_5") (pintype "unspecified"))
    )
    (net (code "15") (name "JS_Y") (class "Default")
      (node (ref "C20") (pin "1") (pinfunction "1_1") (pintype "unspecified"))
      (node (ref "SW11") (pin "5") (pinfunction "DTA_5") (pintype "input"))
      (node (ref "U1") (pin "4") (pinfunction "IO4_4") (pintype "unspecified"))
    )
    (net (code "16") (name "LED1") (class "Default")
      (node (ref "LED4") (pin "2") (pinfunction "A_2") (pintype "unspecified"))
      (node (ref "U1") (pin "8") (pinfunction "IO15_8") (pintype "unspecified"))
    )
    (net (code "17") (name "LED2") (class "Default")
      (node (ref "LED5") (pin "2") (pinfunction "A_2") (pintype "unspecified"))
      (node (ref "U1") (pin "9") (pinfunction "IO16_9") (pintype "unspecified"))
    )
    (net (code "18") (name "Net-(D5-A)") (class "Default")
      (node (ref "D5") (pin "2") (pinfunction "A_2") (pintype "unspecified"))
      (node (ref "U3") (pin "2") (pinfunction "OUTPUT_2") (pintype "unspecified"))
      (node (ref "U3") (pin "4") (pinfunction "OUTPUT_4") (pintype "unspecified"))
    )
    (net (code "19") (name "Net-(D6-A)") (class "Default")
      (node (ref "D6") (pin "2") (pinfunction "A_2") (pintype "unspecified"))
      (node (ref "Q1") (pin "2") (pinfunction "S_2") (pintype "unspecified"))
    )
    (net (code "20") (name "Net-(LED1-K)") (class "Default")
      (node (ref "LED1") (pin "1") (pinfunction "K_1") (pintype "unspecified"))
      (node (ref "R4") (pin "1") (pinfunction "1_1") (pintype "input"))
    )
    (net (code "21") (name "Net-(LED3-A)") (class "Default")
      (node (ref "LED3") (pin "2") (pinfunction "A_2") (pintype "unspecified"))
      (node (ref "R6") (pin "1") (pinfunction "1_1") (pintype "input"))
    )
    (net (code "22") (name "Net-(LED4-K)") (class "Default")
      (node (ref "LED4") (pin "1") (pinfunction "K_1") (pintype "unspecified"))
      (node (ref "R9") (pin "2") (pinfunction "2_2") (pintype "input"))
    )
    (net (code "23") (name "Net-(LED5-K)") (class "Default")
      (node (ref "LED5") (pin "1") (pinfunction "K_1") (pintype "unspecified"))
      (node (ref "R10") (pin "2") (pinfunction "2_2") (pintype "input"))
    )
    (net (code "24") (name "Net-(LED6-K)") (class "Default")
      (node (ref "LED6") (pin "1") (pinfunction "K_1") (pintype "input"))
      (node (ref "R14") (pin "2") (pinfunction "2_2") (pintype "input"))
    )
    (net (code "25") (name "Net-(LED7-K)") (class "Default")
      (node (ref "LED7") (pin "1") (pinfunction "K_1") (pintype "input"))
      (node (ref "R13") (pin "2") (pinfunction "2_2") (pintype "input"))
    )
    (net (code "26") (name "Net-(LED8-K)") (class "Default")
      (node (ref "LED8") (pin "1") (pinfunction "K_1") (pintype "input"))
      (node (ref "R11") (pin "2") (pinfunction "2_2") (pintype "input"))
    )
    (net (code "27") (name "Net-(LED9-K)") (class "Default")
      (node (ref "LED9") (pin "1") (pinfunction "K_1") (pintype "input"))
      (node (ref "R12") (pin "2") (pinfunction "2_2") (pintype "input"))
    )
    (net (code "28") (name "Net-(LED10-K)") (class "Default")
      (node (ref "LED10") (pin "1") (pinfunction "K_1") (pintype "input"))
      (node (ref "R15") (pin "2") (pinfunction "2_2") (pintype "input"))
    )
    (net (code "29") (name "Net-(LED11-K)") (class "Default")
      (node (ref "LED11") (pin "1") (pinfunction "K_1") (pintype "input"))
      (node (ref "R16") (pin "2") (pinfunction "2_2") (pintype "input"))
    )
    (net (code "30") (name "Net-(LED12--)") (class "Default")
      (node (ref "LED12") (pin "2") (pinfunction "-_2") (pintype "unspecified"))
      (node (ref "R17") (pin "2") (pinfunction "2_2") (pintype "input"))
    )
    (net (code "31") (name "Net-(LED13--)") (class "Default")
      (node (ref "LED13") (pin "2") (pinfunction "-_2") (pintype "unspecified"))
      (node (ref "R18") (pin "2") (pinfunction "2_2") (pintype "input"))
    )
    (net (code "32") (name "Net-(Q1-D)") (class "Default")
      (node (ref "C14") (pin "2") (pinfunction "2_2") (pintype "unspecified"))
      (node (ref "Q1") (pin "3") (pinfunction "D_3") (pintype "unspecified"))
      (node (ref "U2") (pin "2") (pinfunction "2_2") (pintype "unspecified"))
      (node (ref "U4") (pin "3") (pinfunction "VBAT_3") (pintype "unspecified"))
    )
    (net (code "33") (name "Net-(U4-PROG)") (class "Default")
      (node (ref "R8") (pin "1") (pinfunction "1_1") (pintype "input"))
      (node (ref "U4") (pin "5") (pinfunction "PROG_5") (pintype "unspecified"))
    )
    (net (code "34") (name "Net-(U4-STAT)") (class "Default")
      (node (ref "R4") (pin "2") (pinfunction "2_2") (pintype "input"))
      (node (ref "R6") (pin "2") (pinfunction "2_2") (pintype "input"))
      (node (ref "U4") (pin "1") (pinfunction "STAT_1") (pintype "unspecified"))
    )
    (net (code "35") (name "PAIR") (class "Default")
      (node (ref "C7") (pin "1") (pinfunction "1_1") (pintype "unspecified"))
      (node (ref "SW4") (pin "4") (pinfunction "4_4") (pintype "unspecified"))
      (node (ref "U1") (pin "10") (pinfunction "IO17_10") (pintype "unspecified"))
    )
    (net (code "36") (name "PILOT") (class "Default")
      (node (ref "C6") (pin "1") (pinfunction "1_1") (pintype "unspecified"))
      (node (ref "SW3") (pin "4") (pinfunction "4_4") (pintype "unspecified"))
      (node (ref "U1") (pin "6") (pinfunction "IO6_6") (pintype "unspecified"))
    )
    (net (code "37") (name "VBAT") (class "Default")
      (node (ref "C9") (pin "2") (pinfunction "2_2") (pintype "unspecified"))
      (node (ref "D6") (pin "1") (pinfunction "K_1") (pintype "unspecified"))
      (node (ref "SW5") (pin "1") (pinfunction "1_1") (pintype "unspecified"))
    )
    (net (code "38") (name "VBUS") (class "Default")
      (node (ref "C11") (pin "2") (pinfunction "2_2") (pintype "unspecified"))
      (node (ref "D1") (pin "2") (pinfunction "A_2") (pintype "unspecified"))
      (node (ref "D2") (pin "2") (pinfunction "2_2") (pintype "unspecified"))
      (node (ref "LED1") (pin "2") (pinfunction "A_2") (pintype "unspecified"))
      (node (ref "Q1") (pin "1") (pinfunction "G_1") (pintype "unspecified"))
      (node (ref "R5") (pin "2") (pinfunction "2_2") (pintype "input"))
      (node (ref "U4") (pin "4") (pinfunction "VDD_4") (pintype "unspecified"))
      (node (ref "USB1") (pin "A4") (pinfunction "VBUS_A4") (pintype "unspecified"))
      (node (ref "USB1") (pin "A9") (pinfunction "VBUS_A9") (pintype "unspecified"))
      (node (ref "USB1") (pin "B4") (pinfunction "VBUS_B4") (pintype "unspecified"))
      (node (ref "USB1") (pin "B9") (pinfunction "VBUS_B9") (pintype "unspecified"))
    )
    (net (code "39") (name "VCC_5V") (class "Default")
      (node (ref "C10") (pin "2") (pinfunction "2_2") (pintype "unspecified"))
      (node (ref "C13") (pin "2") (pinfunction "2_2") (pintype "unspecified"))
      (node (ref "C8") (pin "2") (pinfunction "2_2") (pintype "unspecified"))
      (node (ref "D1") (pin "1") (pinfunction "K_1") (pintype "unspecified"))
      (node (ref "SW5") (pin "2") (pinfunction "2_2") (pintype "unspecified"))
      (node (ref "U3") (pin "3") (pinfunction "INPUT_3") (pintype "unspecified"))
    )
    (net (code "40") (name "unconnected-(SW1-Pad2)") (class "Default")
      (node (ref "SW1") (pin "2") (pinfunction "2_2") (pintype "unspecified+no_connect"))
    )
    (net (code "41") (name "unconnected-(SW1-Pad3)") (class "Default")
      (node (ref "SW1") (pin "3") (pinfunction "3_3") (pintype "unspecified+no_connect"))
    )
    (net (code "42") (name "unconnected-(SW2-Pad2)") (class "Default")
      (node (ref "SW2") (pin "2") (pinfunction "2_2") (pintype "unspecified+no_connect"))
    )
    (net (code "43") (name "unconnected-(SW2-Pad3)") (class "Default")
      (node (ref "SW2") (pin "3") (pinfunction "3_3") (pintype "unspecified+no_connect"))
    )
    (net (code "44") (name "unconnected-(SW3-Pad2)") (class "Default")
      (node (ref "SW3") (pin "2") (pinfunction "2_2") (pintype "unspecified+no_connect"))
    )
    (net (code "45") (name "unconnected-(SW3-Pad3)") (class "Default")
      (node (ref "SW3") (pin "3") (pinfunction "3_3") (pintype "unspecified+no_connect"))
    )
    (net (code "46") (name "unconnected-(SW4-Pad2)") (class "Default")
      (node (ref "SW4") (pin "2") (pinfunction "2_2") (pintype "unspecified+no_connect"))
    )
    (net (code "47") (name "unconnected-(SW4-Pad3)") (class "Default")
      (node (ref "SW4") (pin "3") (pinfunction "3_3") (pintype "unspecified+no_connect"))
    )
    (net (code "48") (name "unconnected-(SW5-Pad0)") (class "Default")
      (node (ref "SW5") (pin "0") (pinfunction "0_0") (pintype "unspecified+no_connect"))
    )
    (net (code "49") (name "unconnected-(SW5-Pad3)") (class "Default")
      (node (ref "SW5") (pin "3") (pinfunction "3_3") (pintype "unspecified"))
    )
    (net (code "50") (name "unconnected-(SW6-Pad2)") (class "Default")
      (node (ref "SW6") (pin "2") (pinfunction "2_2") (pintype "unspecified+no_connect"))
    )
    (net (code "51") (name "unconnected-(SW6-Pad3)") (class "Default")
      (node (ref "SW6") (pin "3") (pinfunction "3_3") (pintype "unspecified+no_connect"))
    )
    (net (code "52") (name "unconnected-(SW7-Pad2)") (class "Default")
      (node (ref "SW7") (pin "2") (pinfunction "2_2") (pintype "unspecified+no_connect"))
    )
    (net (code "53") (name "unconnected-(SW7-Pad3)") (class "Default")
      (node (ref "SW7") (pin "3") (pinfunction "3_3") (pintype "unspecified+no_connect"))
    )
    (net (code "54") (name "unconnected-(SW8-Pad2)") (class "Default")
      (node (ref "SW8") (pin "2") (pinfunction "2_2") (pintype "unspecified+no_connect"))
    )
    (net (code "55") (name "unconnected-(SW8-Pad3)") (class "Default")
      (node (ref "SW8") (pin "3") (pinfunction "3_3") (pintype "unspecified+no_connect"))
    )
    (net (code "56") (name "unconnected-(SW9-Pad2)") (class "Default")
      (node (ref "SW9") (pin "2") (pinfunction "2_2") (pintype "unspecified+no_connect"))
    )
    (net (code "57") (name "unconnected-(SW9-Pad3)") (class "Default")
      (node (ref "SW9") (pin "3") (pinfunction "3_3") (pintype "unspecified+no_connect"))
    )
    (net (code "58") (name "unconnected-(SW11-GND-Pad7)") (class "Default")
      (node (ref "SW11") (pin "7") (pinfunction "GND_7") (pintype "input+no_connect"))
    )
    (net (code "59") (name "unconnected-(SW11-GND-Pad8)") (class "Default")
      (node (ref "SW11") (pin "8") (pinfunction "GND_8") (pintype "input+no_connect"))
    )
    (net (code "60") (name "unconnected-(SW11-GND-Pad9)") (class "Default")
      (node (ref "SW11") (pin "9") (pinfunction "GND_9") (pintype "input+no_connect"))
    )
    (net (code "61") (name "unconnected-(SW11-GND-Pad10)") (class "Default")
      (node (ref "SW11") (pin "10") (pinfunction "GND_10") (pintype "input+no_connect"))
    )
    (net (code "62") (name "unconnected-(SW11-Pada)") (class "Default")
      (node (ref "SW11") (pin "a") (pinfunction "a_a") (pintype "input+no_connect"))
    )
    (net (code "63") (name "unconnected-(SW11-Padd)") (class "Default")
      (node (ref "SW11") (pin "d") (pinfunction "d_d") (pintype "input+no_connect"))
    )
    (net (code "64") (name "unconnected-(U1-IO1-Pad39)") (class "Default")
      (node (ref "U1") (pin "39") (pinfunction "IO1_39") (pintype "unspecified+no_connect"))
    )
    (net (code "65") (name "unconnected-(U1-IO2-Pad38)") (class "Default")
      (node (ref "U1") (pin "38") (pinfunction "IO2_38") (pintype "unspecified+no_connect"))
    )
    (net (code "66") (name "unconnected-(U1-IO3-Pad15)") (class "Default")
      (node (ref "U1") (pin "15") (pinfunction "IO3_15") (pintype "unspecified+no_connect"))
    )
    (net (code "67") (name "unconnected-(U1-IO8-Pad12)") (class "Default")
      (node (ref "U1") (pin "12") (pinfunction "IO8_12") (pintype "unspecified+no_connect"))
    )
    (net (code "68") (name "unconnected-(U1-IO9-Pad17)") (class "Default")
      (node (ref "U1") (pin "17") (pinfunction "IO9_17") (pintype "unspecified+no_connect"))
    )
    (net (code "69") (name "unconnected-(U1-IO10-Pad18)") (class "Default")
      (node (ref "U1") (pin "18") (pinfunction "IO10_18") (pintype "unspecified+no_connect"))
    )
    (net (code "70") (name "unconnected-(U1-IO11-Pad19)") (class "Default")
      (node (ref "U1") (pin "19") (pinfunction "IO11_19") (pintype "unspecified+no_connect"))
    )
    (net (code "71") (name "unconnected-(U1-IO12-Pad20)") (class "Default")
      (node (ref "U1") (pin "20") (pinfunction "IO12_20") (pintype "unspecified+no_connect"))
    )
    (net (code "72") (name "unconnected-(U1-IO13-Pad21)") (class "Default")
      (node (ref "U1") (pin "21") (pinfunction "IO13_21") (pintype "unspecified+no_connect"))
    )
    (net (code "73") (name "unconnected-(U1-IO14-Pad22)") (class "Default")
      (node (ref "U1") (pin "22") (pinfunction "IO14_22") (pintype "unspecified+no_connect"))
    )
    (net (code "74") (name "unconnected-(U1-IO18-Pad11)") (class "Default")
      (node (ref "U1") (pin "11") (pinfunction "IO18_11") (pintype "unspecified+no_connect"))
    )
    (net (code "75") (name "unconnected-(U1-IO21-Pad23)") (class "Default")
      (node (ref "U1") (pin "23") (pinfunction "IO21_23") (pintype "unspecified+no_connect"))
    )
    (net (code "76") (name "unconnected-(U1-IO35-Pad28)") (class "Default")
      (node (ref "U1") (pin "28") (pinfunction "IO35_28") (pintype "unspecified+no_connect"))
    )
    (net (code "77") (name "unconnected-(U1-IO36-Pad29)") (class "Default")
      (node (ref "U1") (pin "29") (pinfunction "IO36_29") (pintype "unspecified+no_connect"))
    )
    (net (code "78") (name "unconnected-(U1-IO37-Pad30)") (class "Default")
      (node (ref "U1") (pin "30") (pinfunction "IO37_30") (pintype "unspecified+no_connect"))
    )
    (net (code "79") (name "unconnected-(U1-IO38-Pad31)") (class "Default")
      (node (ref "U1") (pin "31") (pinfunction "IO38_31") (pintype "unspecified+no_connect"))
    )
    (net (code "80") (name "unconnected-(U1-IO45-Pad26)") (class "Default")
      (node (ref "U1") (pin "26") (pinfunction "IO45_26") (pintype "unspecified+no_connect"))
    )
    (net (code "81") (name "unconnected-(U1-IO46-Pad16)") (class "Default")
      (node (ref "U1") (pin "16") (pinfunction "IO46_16") (pintype "unspecified+no_connect"))
    )
    (net (code "82") (name "unconnected-(U1-IO47-Pad24)") (class "Default")
      (node (ref "U1") (pin "24") (pinfunction "IO47_24") (pintype "unspecified+no_connect"))
    )
    (net (code "83") (name "unconnected-(U1-IO48-Pad25)") (class "Default")
      (node (ref "U1") (pin "25") (pinfunction "IO48_25") (pintype "unspecified+no_connect"))
    )
    (net (code "84") (name "unconnected-(U1-RXD0-Pad36)") (class "Default")
      (node (ref "U1") (pin "36") (pinfunction "RXD0_36") (pintype "unspecified+no_connect"))
    )
    (net (code "85") (name "unconnected-(U1-TXD0-Pad37)") (class "Default")
      (node (ref "U1") (pin "37") (pinfunction "TXD0_37") (pintype "unspecified+no_connect"))
    )
    (net (code "86") (name "unconnected-(USB1-SBU1-PadA8)") (class "Default")
      (node (ref "USB1") (pin "A8") (pinfunction "SBU1_A8") (pintype "unspecified+no_connect"))
    )
    (net (code "87") (name "unconnected-(USB1-SBU2-PadB8)") (class "Default")
      (node (ref "USB1") (pin "B8") (pinfunction "SBU2_B8") (pintype "unspecified+no_connect"))
    )
    (net (code "88") (name "unconnected-(USB1-SH-Pad0)") (class "Default")
      (node (ref "USB1") (pin "0") (pinfunction "SH_0") (pintype "unspecified+no_connect"))
    )
    (net (code "89") (name "unconnected-(USB1-SH-Pad1)") (class "Default")
      (node (ref "USB1") (pin "1") (pinfunction "SH_1") (pintype "unspecified+no_connect"))
    )
    (net (code "90") (name "unconnected-(USB1-SH-Pad2)") (class "Default")
      (node (ref "USB1") (pin "2") (pinfunction "SH_2") (pintype "unspecified+no_connect"))
    )
    (net (code "91") (name "unconnected-(USB1-SH-Pad3)") (class "Default")
      (node (ref "USB1") (pin "3") (pinfunction "SH_3") (pintype "unspecified+no_connect"))
    )
  )
)
